# sx1509-breakout_mount_remap5.net
KiCad netlist of a schematic drawn in EAGLE
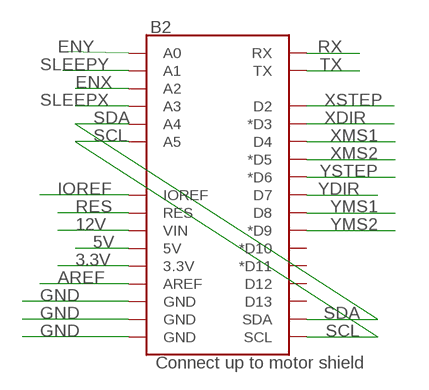
[diagram p0: schematic, sheet 1, part 1 of 2]
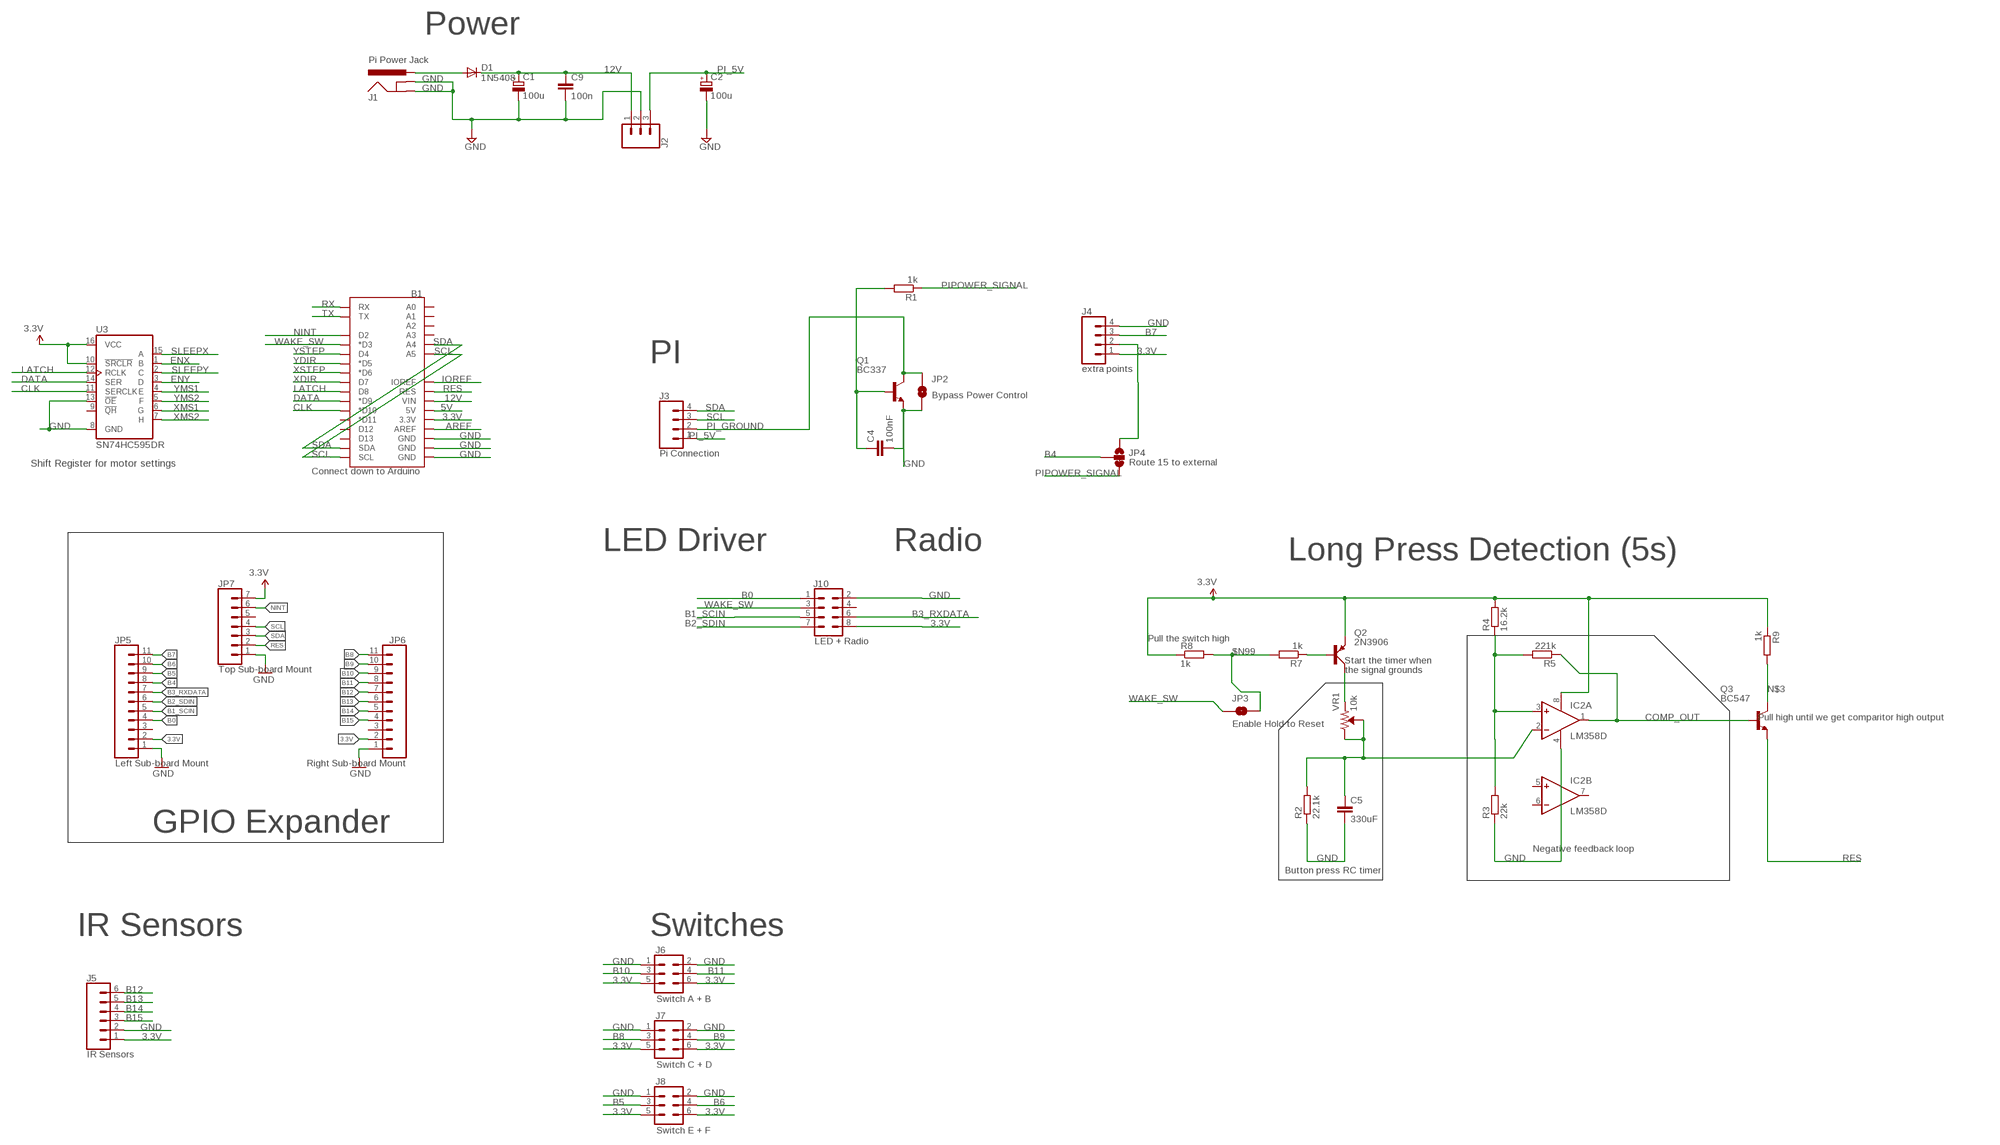
[diagram p1: schematic, sheet 1, part 2 of 2]

(export (version "E")
  (design (tool "Eeschema 10.0.6"))
  (components
    (comp (ref "B1")
      (value "Connect down to Arduino")
      (footprint "eagle-import:UNO_R3_SHIELD_NOLABELS")
      (libsource (lib "eagle-import") (part "ARDUINO_UNO_R3_SHIELDNOLABELS"))
    )
    (comp (ref "B2")
      (value "Connect up to motor shield")
      (footprint "eagle-import:UNO_R3_SHIELD_NOLABELS")
      (libsource (lib "eagle-import") (part "ARDUINO_UNO_R3_SHIELDNOLABELS"))
    )
    (comp (ref "C1")
      (value "100u")
      (footprint "eagle-import:E2-5")
      (libsource (lib "eagle-import") (part "CPOL-EUE2-5"))
    )
    (comp (ref "C2")
      (value "100u")
      (footprint "eagle-import:E2-5")
      (libsource (lib "eagle-import") (part "CPOL-EUE2-5"))
    )
    (comp (ref "C4")
      (value "100nF")
      (footprint "eagle-import:C0805")
      (libsource (lib "eagle-import") (part "resistor_348_C-EUC0805"))
    )
    (comp (ref "C5")
      (value "330uF")
      (footprint "eagle-import:C0805")
      (libsource (lib "eagle-import") (part "resistor_348_C-EUC0805"))
    )
    (comp (ref "C9")
      (value "100n")
      (footprint "eagle-import:C0805")
      (libsource (lib "eagle-import") (part "C-EUC0805"))
    )
    (comp (ref "D1")
      (value "1N5408")
      (footprint "eagle-import:DO15-12")
      (libsource (lib "eagle-import") (part "1N5408"))
    )
    (comp (ref "IC2")
      (value "LM358D")
      (footprint "eagle-import:SO08")
      (libsource (lib "eagle-import") (part "LM358D"))
    )
    (comp (ref "J1")
      (value "Pi Power Jack")
      (footprint "eagle-import:POWER_JACK_PTH_BREAD")
      (libsource (lib "eagle-import") (part "POWER_JACKPTH_BREAD"))
    )
    (comp (ref "J2")
      (value "Header - Right angled, female")
      (footprint "eagle-import:1X03")
      (libsource (lib "eagle-import") (part "CONN_031X03_2.54MM_RA_FEMALE"))
    )
    (comp (ref "J3")
      (value "Pi Connection")
      (footprint "eagle-import:1X04_1.24MM_RA_MALE")
      (libsource (lib "eagle-import") (part "CONN_041X04_1.24MM_RA_MALE"))
    )
    (comp (ref "J4")
      (value "extra points")
      (footprint "eagle-import:1X04_1.24MM_RA_MALE")
      (libsource (lib "eagle-import") (part "CONN_041X04_1.24MM_RA_MALE"))
    )
    (comp (ref "J5")
      (value "IR Sensors")
      (footprint "eagle-import:1X06")
      (libsource (lib "eagle-import") (part "CONN_06SILK_FEMALE_PTH"))
    )
    (comp (ref "J6")
      (value "Switch A + B")
      (footprint "eagle-import:2X3")
      (libsource (lib "eagle-import") (part "CONN_03X22X03_2.54MM_RA_MALE"))
    )
    (comp (ref "J7")
      (value "Switch C + D")
      (footprint "eagle-import:2X3")
      (libsource (lib "eagle-import") (part "CONN_03X22X03_2.54MM_RA_MALE"))
    )
    (comp (ref "J8")
      (value "Switch E + F")
      (footprint "eagle-import:2X3")
      (libsource (lib "eagle-import") (part "CONN_03X22X03_2.54MM_RA_MALE"))
    )
    (comp (ref "J10")
      (value "LED + Radio")
      (footprint "eagle-import:2X4")
      (libsource (lib "eagle-import") (part "CONN_04X22X4_1.24MM_RA_MALE"))
    )
    (comp (ref "JP2")
      (value "Bypass Power Control")
      (footprint "eagle-import:SMT-JUMPER_2_NO_SILK_ROUND")
      (libsource (lib "eagle-import") (part "JUMPER-SMT_2_NO_SILK_ROUND"))
    )
    (comp (ref "JP3")
      (value "Enable Hold to Reset")
      (footprint "eagle-import:SMT-JUMPER_2_NC_TRACE_SILK")
      (libsource (lib "eagle-import") (part "JUMPER-SMT_2_NC_TRACE_SILK"))
    )
    (comp (ref "JP4")
      (value "Route 15 to external")
      (footprint "eagle-import:SMT-JUMPER_3_1-NC_TRACE_SILK")
      (libsource (lib "eagle-import") (part "JUMPER-SMT_3_1-NC_TRACE_SILK"))
    )
    (comp (ref "JP5")
      (value "Left Sub-board Mount")
      (footprint "eagle-import:1X11")
      (libsource (lib "eagle-import") (part "CONN_111X11_2.54MM_FEMALE"))
    )
    (comp (ref "JP6")
      (value "Right Sub-board Mount")
      (footprint "eagle-import:1X11")
      (libsource (lib "eagle-import") (part "CONN_111X11_2.54MM_FEMALE"))
    )
    (comp (ref "JP7")
      (value "Top Sub-board Mount")
      (footprint "eagle-import:1X07")
      (libsource (lib "eagle-import") (part "CONN_071X07_2.54MM_FEMALE"))
    )
    (comp (ref "Q1")
      (value "BC337")
      (footprint "eagle-import:TO92")
      (libsource (lib "eagle-import") (part "BC337"))
    )
    (comp (ref "Q2")
      (value "2N3906")
      (footprint "eagle-import:TO92D")
      (libsource (lib "eagle-import") (part "2N3906"))
    )
    (comp (ref "Q3")
      (value "BC547")
      (footprint "eagle-import:TO92")
      (fields (field (name "NOTE") "Pull high until we get comparitor high output"))
      (libsource (lib "eagle-import") (part "BC547"))
    )
    (comp (ref "R1")
      (value "1k")
      (footprint "eagle-import:M0805")
      (libsource (lib "eagle-import") (part "R-EU_M0805"))
    )
    (comp (ref "R2")
      (value "22.1k")
      (footprint "eagle-import:M0805")
      (libsource (lib "eagle-import") (part "R-EU_M0805"))
    )
    (comp (ref "R3")
      (value "22k")
      (footprint "eagle-import:M0805")
      (libsource (lib "eagle-import") (part "R-EU_M0805"))
    )
    (comp (ref "R4")
      (value "16.2k")
      (footprint "eagle-import:M0805")
      (libsource (lib "eagle-import") (part "R-EU_M0805"))
    )
    (comp (ref "R5")
      (value "221k")
      (footprint "eagle-import:M0805")
      (libsource (lib "eagle-import") (part "R-EU_M0805"))
    )
    (comp (ref "R7")
      (value "1k")
      (footprint "eagle-import:M0805")
      (libsource (lib "eagle-import") (part "R-EU_M0805"))
    )
    (comp (ref "R8")
      (value "1k")
      (footprint "eagle-import:M0805")
      (fields (field (name "NOTE") "Pull the switch high"))
      (libsource (lib "eagle-import") (part "R-EU_M0805"))
    )
    (comp (ref "R9")
      (value "1k")
      (footprint "eagle-import:M0805")
      (libsource (lib "eagle-import") (part "R-EU_M0805"))
    )
    (comp (ref "U3")
      (value "SN74HC595DR")
      (footprint "eagle-import:SO16")
      (libsource (lib "eagle-import") (part "SN74HC595DHC"))
    )
    (comp (ref "VR1")
      (value "10k")
      (footprint "eagle-import:TRIMPOT-PTH-3386U")
      (libsource (lib "eagle-import") (part "TRIMPOT-PTH-10MM-KNOB-1/2W-10%"))
    )
  )
  (nets
    (net (code "1") (name "/$N99") (class "Default")
      (node (ref "JP3") (pin "2") (pinfunction "2_2") (pintype "passive"))
      (node (ref "R7") (pin "2") (pinfunction "2_2") (pintype "passive"))
      (node (ref "R8") (pin "2") (pinfunction "2_2") (pintype "passive"))
    )
    (net (code "2") (name "/5V") (class "Default")
      (node (ref "B1") (pin "5V") (pinfunction "5V_5V") (pintype "bidirectional"))
      (node (ref "B2") (pin "5V") (pinfunction "5V_5V") (pintype "bidirectional"))
    )
    (net (code "3") (name "/12V") (class "Default")
      (node (ref "B1") (pin "VIN") (pinfunction "VIN_VIN") (pintype "bidirectional"))
      (node (ref "B2") (pin "VIN") (pinfunction "VIN_VIN") (pintype "bidirectional"))
      (node (ref "C1") (pin "+") (pinfunction "+_+") (pintype "passive"))
      (node (ref "C9") (pin "1") (pinfunction "1_1") (pintype "passive"))
      (node (ref "D1") (pin "C") (pinfunction "C_C") (pintype "passive"))
      (node (ref "J2") (pin "1") (pinfunction "1_1") (pintype "passive"))
    )
    (net (code "4") (name "/AREF") (class "Default")
      (node (ref "B1") (pin "AREF") (pinfunction "AREF_AREF") (pintype "bidirectional"))
      (node (ref "B2") (pin "AREF") (pinfunction "AREF_AREF") (pintype "bidirectional"))
    )
    (net (code "5") (name "/CLK") (class "Default")
      (node (ref "B1") (pin "D10") (pinfunction "*D10_D10") (pintype "bidirectional"))
      (node (ref "U3") (pin "11") (pinfunction "SERCLK_11") (pintype "input"))
    )
    (net (code "6") (name "/COMP_OUT") (class "Default")
      (node (ref "IC2") (pin "1") (pinfunction "OUT_1") (pintype "output"))
      (node (ref "Q3") (pin "2") (pinfunction "B_2") (pintype "passive"))
      (node (ref "R5") (pin "1") (pinfunction "1_1") (pintype "passive"))
    )
    (net (code "7") (name "/DATA") (class "Default")
      (node (ref "B1") (pin "D9") (pinfunction "*D9_D9") (pintype "bidirectional"))
      (node (ref "U3") (pin "14") (pinfunction "SER_14") (pintype "input"))
    )
    (net (code "8") (name "/ENX") (class "Default")
      (node (ref "B2") (pin "A2") (pinfunction "A2_A2") (pintype "bidirectional"))
      (node (ref "U3") (pin "1") (pinfunction "B_1") (pintype "tri_state"))
    )
    (net (code "9") (name "/ENY") (class "Default")
      (node (ref "B2") (pin "A0") (pinfunction "A0_A0") (pintype "bidirectional"))
      (node (ref "U3") (pin "3") (pinfunction "D_3") (pintype "tri_state"))
    )
    (net (code "10") (name "/IOREF") (class "Default")
      (node (ref "B1") (pin "IOREF") (pinfunction "IOREF_IOREF") (pintype "bidirectional"))
      (node (ref "B2") (pin "IOREF") (pinfunction "IOREF_IOREF") (pintype "bidirectional"))
    )
    (net (code "11") (name "/LATCH") (class "Default")
      (node (ref "B1") (pin "D8") (pinfunction "D8_D8") (pintype "bidirectional"))
      (node (ref "U3") (pin "12") (pinfunction "RCLK_12") (pintype "input"))
    )
    (net (code "12") (name "/N$3") (class "Default")
      (node (ref "Q3") (pin "3") (pinfunction "C_3") (pintype "passive"))
      (node (ref "R9") (pin "2") (pinfunction "2_2") (pintype "passive"))
    )
    (net (code "13") (name "/PIPOWER_SIGNAL") (class "Default")
      (node (ref "JP4") (pin "3") (pinfunction "3_3") (pintype "passive"))
      (node (ref "R1") (pin "1") (pinfunction "1_1") (pintype "passive"))
    )
    (net (code "14") (name "/PI_5V") (class "Default")
      (node (ref "C2") (pin "+") (pinfunction "+_+") (pintype "passive"))
      (node (ref "J2") (pin "3") (pinfunction "3_3") (pintype "passive"))
      (node (ref "J3") (pin "1") (pinfunction "1_1") (pintype "passive"))
    )
    (net (code "15") (name "/PI_GROUND") (class "Default")
      (node (ref "J3") (pin "2") (pinfunction "2_2") (pintype "passive"))
      (node (ref "JP2") (pin "1") (pinfunction "1_1") (pintype "passive"))
      (node (ref "Q1") (pin "3") (pinfunction "C_3") (pintype "passive"))
    )
    (net (code "16") (name "/RX") (class "Default")
      (node (ref "B1") (pin "RX") (pinfunction "RX_RX") (pintype "bidirectional"))
      (node (ref "B2") (pin "RX") (pinfunction "RX_RX") (pintype "bidirectional"))
    )
    (net (code "17") (name "/SLEEPX") (class "Default")
      (node (ref "B2") (pin "A3") (pinfunction "A3_A3") (pintype "bidirectional"))
      (node (ref "U3") (pin "15") (pinfunction "A_15") (pintype "tri_state"))
    )
    (net (code "18") (name "/SLEEPY") (class "Default")
      (node (ref "B2") (pin "A1") (pinfunction "A1_A1") (pintype "bidirectional"))
      (node (ref "U3") (pin "2") (pinfunction "C_2") (pintype "tri_state"))
    )
    (net (code "19") (name "/TX") (class "Default")
      (node (ref "B1") (pin "TX") (pinfunction "TX_TX") (pintype "bidirectional"))
      (node (ref "B2") (pin "TX") (pinfunction "TX_TX") (pintype "bidirectional"))
    )
    (net (code "20") (name "/WAKE_SW") (class "Default")
      (node (ref "B1") (pin "D3") (pinfunction "*D3_D3") (pintype "bidirectional"))
      (node (ref "J10") (pin "3") (pinfunction "3_3") (pintype "passive"))
      (node (ref "JP3") (pin "1") (pinfunction "1_1") (pintype "passive"))
    )
    (net (code "21") (name "/XDIR") (class "Default")
      (node (ref "B1") (pin "D7") (pinfunction "D7_D7") (pintype "bidirectional"))
      (node (ref "B2") (pin "D3") (pinfunction "*D3_D3") (pintype "bidirectional"))
    )
    (net (code "22") (name "/XMS1") (class "Default")
      (node (ref "B2") (pin "D4") (pinfunction "D4_D4") (pintype "bidirectional"))
      (node (ref "U3") (pin "6") (pinfunction "G_6") (pintype "tri_state"))
    )
    (net (code "23") (name "/XMS2") (class "Default")
      (node (ref "B2") (pin "D5") (pinfunction "*D5_D5") (pintype "bidirectional"))
      (node (ref "U3") (pin "7") (pinfunction "H_7") (pintype "tri_state"))
    )
    (net (code "24") (name "/XSTEP") (class "Default")
      (node (ref "B1") (pin "D6") (pinfunction "*D6_D6") (pintype "bidirectional"))
      (node (ref "B2") (pin "D2") (pinfunction "D2_D2") (pintype "bidirectional"))
    )
    (net (code "25") (name "/YDIR") (class "Default")
      (node (ref "B1") (pin "D5") (pinfunction "*D5_D5") (pintype "bidirectional"))
      (node (ref "B2") (pin "D7") (pinfunction "D7_D7") (pintype "bidirectional"))
    )
    (net (code "26") (name "/YMS1") (class "Default")
      (node (ref "B2") (pin "D8") (pinfunction "D8_D8") (pintype "bidirectional"))
      (node (ref "U3") (pin "4") (pinfunction "E_4") (pintype "tri_state"))
    )
    (net (code "27") (name "/YMS2") (class "Default")
      (node (ref "B2") (pin "D9") (pinfunction "*D9_D9") (pintype "bidirectional"))
      (node (ref "U3") (pin "5") (pinfunction "F_5") (pintype "tri_state"))
    )
    (net (code "28") (name "/YSTEP") (class "Default")
      (node (ref "B1") (pin "D4") (pinfunction "D4_D4") (pintype "bidirectional"))
      (node (ref "B2") (pin "D6") (pinfunction "*D6_D6") (pintype "bidirectional"))
    )
    (net (code "29") (name "3.3V") (class "Default")
      (node (ref "B1") (pin "3.3V") (pinfunction "3.3V_3.3V") (pintype "bidirectional"))
      (node (ref "B2") (pin "3.3V") (pinfunction "3.3V_3.3V") (pintype "bidirectional"))
      (node (ref "IC2") (pin "8") (pinfunction "V+_8") (pintype "power_in"))
      (node (ref "J10") (pin "8") (pinfunction "8_8") (pintype "passive"))
      (node (ref "J4") (pin "1") (pinfunction "1_1") (pintype "passive"))
      (node (ref "J5") (pin "1") (pinfunction "1_1") (pintype "passive"))
      (node (ref "J6") (pin "5") (pinfunction "5_5") (pintype "bidirectional"))
      (node (ref "J6") (pin "6") (pinfunction "6_6") (pintype "bidirectional"))
      (node (ref "J7") (pin "5") (pinfunction "5_5") (pintype "bidirectional"))
      (node (ref "J7") (pin "6") (pinfunction "6_6") (pintype "bidirectional"))
      (node (ref "J8") (pin "5") (pinfunction "5_5") (pintype "bidirectional"))
      (node (ref "J8") (pin "6") (pinfunction "6_6") (pintype "bidirectional"))
      (node (ref "JP5") (pin "2") (pinfunction "2_2") (pintype "passive"))
      (node (ref "JP6") (pin "2") (pinfunction "2_2") (pintype "passive"))
      (node (ref "JP7") (pin "7") (pinfunction "7_7") (pintype "passive"))
      (node (ref "Q2") (pin "E") (pinfunction "E_E") (pintype "passive"))
      (node (ref "R4") (pin "2") (pinfunction "2_2") (pintype "passive"))
      (node (ref "R8") (pin "1") (pinfunction "1_1") (pintype "passive"))
      (node (ref "R9") (pin "1") (pinfunction "1_1") (pintype "passive"))
      (node (ref "U3") (pin "10") (pinfunction "~{SRCLR}_10") (pintype "input"))
      (node (ref "U3") (pin "16") (pinfunction "VCC_16") (pintype "power_in"))
    )
    (net (code "30") (name "B0") (class "Default")
      (node (ref "J10") (pin "1") (pinfunction "1_1") (pintype "passive"))
      (node (ref "JP5") (pin "4") (pinfunction "4_4") (pintype "passive"))
    )
    (net (code "31") (name "B1_SCIN") (class "Default")
      (node (ref "J10") (pin "5") (pinfunction "5_5") (pintype "passive"))
      (node (ref "JP5") (pin "5") (pinfunction "5_5") (pintype "passive"))
    )
    (net (code "32") (name "B2_SDIN") (class "Default")
      (node (ref "J10") (pin "7") (pinfunction "7_7") (pintype "passive"))
      (node (ref "JP5") (pin "6") (pinfunction "6_6") (pintype "passive"))
    )
    (net (code "33") (name "B3_RXDATA") (class "Default")
      (node (ref "J10") (pin "6") (pinfunction "6_6") (pintype "passive"))
      (node (ref "JP5") (pin "7") (pinfunction "7_7") (pintype "passive"))
    )
    (net (code "34") (name "B4") (class "Default")
      (node (ref "JP4") (pin "2") (pinfunction "2_2") (pintype "passive"))
      (node (ref "JP5") (pin "8") (pinfunction "8_8") (pintype "passive"))
    )
    (net (code "35") (name "B5") (class "Default")
      (node (ref "J8") (pin "3") (pinfunction "3_3") (pintype "bidirectional"))
      (node (ref "JP5") (pin "9") (pinfunction "9_9") (pintype "passive"))
    )
    (net (code "36") (name "B6") (class "Default")
      (node (ref "J8") (pin "4") (pinfunction "4_4") (pintype "bidirectional"))
      (node (ref "JP5") (pin "10") (pinfunction "10_10") (pintype "passive"))
    )
    (net (code "37") (name "B7") (class "Default")
      (node (ref "J4") (pin "3") (pinfunction "3_3") (pintype "passive"))
      (node (ref "JP5") (pin "11") (pinfunction "11_11") (pintype "passive"))
    )
    (net (code "38") (name "B8") (class "Default")
      (node (ref "J7") (pin "3") (pinfunction "3_3") (pintype "bidirectional"))
      (node (ref "JP6") (pin "11") (pinfunction "11_11") (pintype "passive"))
    )
    (net (code "39") (name "B9") (class "Default")
      (node (ref "J7") (pin "4") (pinfunction "4_4") (pintype "bidirectional"))
      (node (ref "JP6") (pin "10") (pinfunction "10_10") (pintype "passive"))
    )
    (net (code "40") (name "B10") (class "Default")
      (node (ref "J6") (pin "3") (pinfunction "3_3") (pintype "bidirectional"))
      (node (ref "JP6") (pin "9") (pinfunction "9_9") (pintype "passive"))
    )
    (net (code "41") (name "B11") (class "Default")
      (node (ref "J6") (pin "4") (pinfunction "4_4") (pintype "bidirectional"))
      (node (ref "JP6") (pin "8") (pinfunction "8_8") (pintype "passive"))
    )
    (net (code "42") (name "B12") (class "Default")
      (node (ref "J5") (pin "6") (pinfunction "6_6") (pintype "passive"))
      (node (ref "JP6") (pin "7") (pinfunction "7_7") (pintype "passive"))
    )
    (net (code "43") (name "B13") (class "Default")
      (node (ref "J5") (pin "5") (pinfunction "5_5") (pintype "passive"))
      (node (ref "JP6") (pin "6") (pinfunction "6_6") (pintype "passive"))
    )
    (net (code "44") (name "B14") (class "Default")
      (node (ref "J5") (pin "4") (pinfunction "4_4") (pintype "passive"))
      (node (ref "JP6") (pin "5") (pinfunction "5_5") (pintype "passive"))
    )
    (net (code "45") (name "B15") (class "Default")
      (node (ref "J5") (pin "3") (pinfunction "3_3") (pintype "passive"))
      (node (ref "JP6") (pin "4") (pinfunction "4_4") (pintype "passive"))
    )
    (net (code "46") (name "GND") (class "Default")
      (node (ref "B1") (pin "GND@0") (pinfunction "GND_GND@0") (pintype "bidirectional"))
      (node (ref "B1") (pin "GND@1") (pinfunction "GND_GND@1") (pintype "bidirectional"))
      (node (ref "B1") (pin "GND@2") (pinfunction "GND_GND@2") (pintype "bidirectional"))
      (node (ref "B2") (pin "GND@0") (pinfunction "GND_GND@0") (pintype "bidirectional"))
      (node (ref "B2") (pin "GND@1") (pinfunction "GND_GND@1") (pintype "bidirectional"))
      (node (ref "B2") (pin "GND@2") (pinfunction "GND_GND@2") (pintype "bidirectional"))
      (node (ref "C1") (pin "-") (pinfunction "-_-") (pintype "passive"))
      (node (ref "C2") (pin "-") (pinfunction "-_-") (pintype "passive"))
      (node (ref "C4") (pin "2") (pinfunction "2_2") (pintype "passive"))
      (node (ref "C5") (pin "2") (pinfunction "2_2") (pintype "passive"))
      (node (ref "C9") (pin "2") (pinfunction "2_2") (pintype "passive"))
      (node (ref "IC2") (pin "4") (pinfunction "V-_4") (pintype "power_in"))
      (node (ref "J1") (pin "GND") (pinfunction "GND_GND") (pintype "bidirectional"))
      (node (ref "J1") (pin "GNDBREAK") (pinfunction "GNDBREAK_GNDBREAK") (pintype "bidirectional"))
      (node (ref "J10") (pin "2") (pinfunction "2_2") (pintype "passive"))
      (node (ref "J2") (pin "2") (pinfunction "2_2") (pintype "passive"))
      (node (ref "J4") (pin "4") (pinfunction "4_4") (pintype "passive"))
      (node (ref "J5") (pin "2") (pinfunction "2_2") (pintype "passive"))
      (node (ref "J6") (pin "1") (pinfunction "1_1") (pintype "bidirectional"))
      (node (ref "J6") (pin "2") (pinfunction "2_2") (pintype "bidirectional"))
      (node (ref "J7") (pin "1") (pinfunction "1_1") (pintype "bidirectional"))
      (node (ref "J7") (pin "2") (pinfunction "2_2") (pintype "bidirectional"))
      (node (ref "J8") (pin "1") (pinfunction "1_1") (pintype "bidirectional"))
      (node (ref "J8") (pin "2") (pinfunction "2_2") (pintype "bidirectional"))
      (node (ref "JP2") (pin "2") (pinfunction "2_2") (pintype "passive"))
      (node (ref "JP5") (pin "1") (pinfunction "1_1") (pintype "passive"))
      (node (ref "JP6") (pin "1") (pinfunction "1_1") (pintype "passive"))
      (node (ref "JP7") (pin "1") (pinfunction "1_1") (pintype "passive"))
      (node (ref "Q1") (pin "1") (pinfunction "E_1") (pintype "passive"))
      (node (ref "R2") (pin "1") (pinfunction "1_1") (pintype "passive"))
      (node (ref "R3") (pin "1") (pinfunction "1_1") (pintype "passive"))
      (node (ref "U3") (pin "13") (pinfunction "~{OE}_13") (pintype "input"))
      (node (ref "U3") (pin "8") (pinfunction "GND_8") (pintype "power_in"))
    )
    (net (code "47") (name "NINT") (class "Default")
      (node (ref "B1") (pin "D2") (pinfunction "D2_D2") (pintype "bidirectional"))
      (node (ref "JP7") (pin "6") (pinfunction "6_6") (pintype "passive"))
    )
    (net (code "48") (name "Net-(D1-PadA)") (class "Default")
      (node (ref "D1") (pin "A") (pinfunction "A_A") (pintype "passive"))
      (node (ref "J1") (pin "PWR") (pinfunction "PWR_PWR") (pintype "bidirectional"))
    )
    (net (code "49") (name "Net-(IC2A-+IN)") (class "Default")
      (node (ref "IC2") (pin "3") (pinfunction "+IN_3") (pintype "input"))
      (node (ref "R3") (pin "2") (pinfunction "2_2") (pintype "passive"))
      (node (ref "R4") (pin "1") (pinfunction "1_1") (pintype "passive"))
      (node (ref "R5") (pin "2") (pinfunction "2_2") (pintype "passive"))
    )
    (net (code "50") (name "Net-(IC2A--IN)") (class "Default")
      (node (ref "C5") (pin "1") (pinfunction "1_1") (pintype "passive"))
      (node (ref "IC2") (pin "2") (pinfunction "-IN_2") (pintype "input"))
      (node (ref "R2") (pin "2") (pinfunction "2_2") (pintype "passive"))
      (node (ref "VR1") (pin "2") (pinfunction "WIPER_2") (pintype "passive"))
      (node (ref "VR1") (pin "3") (pinfunction "CW_3") (pintype "passive"))
    )
    (net (code "51") (name "Net-(J4-Pad2)") (class "Default")
      (node (ref "J4") (pin "2") (pinfunction "2_2") (pintype "passive"))
      (node (ref "JP4") (pin "1") (pinfunction "1_1") (pintype "passive"))
    )
    (net (code "52") (name "Net-(Q1-B)") (class "Default")
      (node (ref "C4") (pin "1") (pinfunction "1_1") (pintype "passive"))
      (node (ref "Q1") (pin "2") (pinfunction "B_2") (pintype "passive"))
      (node (ref "R1") (pin "2") (pinfunction "2_2") (pintype "passive"))
    )
    (net (code "53") (name "Net-(Q2-PadB)") (class "Default")
      (node (ref "Q2") (pin "B") (pinfunction "B_B") (pintype "passive"))
      (node (ref "R7") (pin "1") (pinfunction "1_1") (pintype "passive"))
    )
    (net (code "54") (name "Net-(VR1-CCW)") (class "Default")
      (node (ref "Q2") (pin "C") (pinfunction "C_C") (pintype "passive"))
      (node (ref "VR1") (pin "1") (pinfunction "CCW_1") (pintype "passive"))
    )
    (net (code "55") (name "RES") (class "Default")
      (node (ref "B1") (pin "RES") (pinfunction "RES_RES") (pintype "bidirectional"))
      (node (ref "B2") (pin "RES") (pinfunction "RES_RES") (pintype "bidirectional"))
      (node (ref "JP7") (pin "2") (pinfunction "2_2") (pintype "passive"))
      (node (ref "Q3") (pin "1") (pinfunction "E_1") (pintype "passive"))
    )
    (net (code "56") (name "SCL") (class "Default")
      (node (ref "B1") (pin "A5") (pinfunction "A5_A5") (pintype "bidirectional"))
      (node (ref "B1") (pin "SCL") (pinfunction "SCL_SCL") (pintype "bidirectional"))
      (node (ref "B2") (pin "A5") (pinfunction "A5_A5") (pintype "bidirectional"))
      (node (ref "B2") (pin "SCL") (pinfunction "SCL_SCL") (pintype "bidirectional"))
      (node (ref "J3") (pin "3") (pinfunction "3_3") (pintype "passive"))
      (node (ref "JP7") (pin "4") (pinfunction "4_4") (pintype "passive"))
    )
    (net (code "57") (name "SDA") (class "Default")
      (node (ref "B1") (pin "A4") (pinfunction "A4_A4") (pintype "bidirectional"))
      (node (ref "B1") (pin "SDA") (pinfunction "SDA_SDA") (pintype "bidirectional"))
      (node (ref "B2") (pin "A4") (pinfunction "A4_A4") (pintype "bidirectional"))
      (node (ref "B2") (pin "SDA") (pinfunction "SDA_SDA") (pintype "bidirectional"))
      (node (ref "J3") (pin "4") (pinfunction "4_4") (pintype "passive"))
      (node (ref "JP7") (pin "3") (pinfunction "3_3") (pintype "passive"))
    )
    (net (code "58") (name "unconnected-(B1-*D11-PadD11)") (class "Default")
      (node (ref "B1") (pin "D11") (pinfunction "*D11_D11") (pintype "bidirectional"))
    )
    (net (code "59") (name "unconnected-(B1-PadA0)") (class "Default")
      (node (ref "B1") (pin "A0") (pinfunction "A0_A0") (pintype "bidirectional"))
    )
    (net (code "60") (name "unconnected-(B1-PadA1)") (class "Default")
      (node (ref "B1") (pin "A1") (pinfunction "A1_A1") (pintype "bidirectional"))
    )
    (net (code "61") (name "unconnected-(B1-PadA2)") (class "Default")
      (node (ref "B1") (pin "A2") (pinfunction "A2_A2") (pintype "bidirectional"))
    )
    (net (code "62") (name "unconnected-(B1-PadA3)") (class "Default")
      (node (ref "B1") (pin "A3") (pinfunction "A3_A3") (pintype "bidirectional"))
    )
    (net (code "63") (name "unconnected-(B1-PadD12)") (class "Default")
      (node (ref "B1") (pin "D12") (pinfunction "D12_D12") (pintype "bidirectional"))
    )
    (net (code "64") (name "unconnected-(B1-PadD13)") (class "Default")
      (node (ref "B1") (pin "D13") (pinfunction "D13_D13") (pintype "bidirectional"))
    )
    (net (code "65") (name "unconnected-(B2-*D10-PadD10)") (class "Default")
      (node (ref "B2") (pin "D10") (pinfunction "*D10_D10") (pintype "bidirectional"))
    )
    (net (code "66") (name "unconnected-(B2-*D11-PadD11)") (class "Default")
      (node (ref "B2") (pin "D11") (pinfunction "*D11_D11") (pintype "bidirectional"))
    )
    (net (code "67") (name "unconnected-(B2-PadD12)") (class "Default")
      (node (ref "B2") (pin "D12") (pinfunction "D12_D12") (pintype "bidirectional"))
    )
    (net (code "68") (name "unconnected-(B2-PadD13)") (class "Default")
      (node (ref "B2") (pin "D13") (pinfunction "D13_D13") (pintype "bidirectional"))
    )
    (net (code "69") (name "unconnected-(IC2B-+IN-Pad5)") (class "Default")
      (node (ref "IC2") (pin "5") (pinfunction "+IN_5") (pintype "input"))
    )
    (net (code "70") (name "unconnected-(IC2B--IN-Pad6)") (class "Default")
      (node (ref "IC2") (pin "6") (pinfunction "-IN_6") (pintype "input"))
    )
    (net (code "71") (name "unconnected-(IC2B-OUT-Pad7)") (class "Default")
      (node (ref "IC2") (pin "7") (pinfunction "OUT_7") (pintype "output"))
    )
    (net (code "72") (name "unconnected-(J10-Pad4)") (class "Default")
      (node (ref "J10") (pin "4") (pinfunction "4_4") (pintype "passive"))
    )
    (net (code "73") (name "unconnected-(JP5-Pad3)") (class "Default")
      (node (ref "JP5") (pin "3") (pinfunction "3_3") (pintype "passive"))
    )
    (net (code "74") (name "unconnected-(JP6-Pad3)") (class "Default")
      (node (ref "JP6") (pin "3") (pinfunction "3_3") (pintype "passive"))
    )
    (net (code "75") (name "unconnected-(JP7-Pad5)") (class "Default")
      (node (ref "JP7") (pin "5") (pinfunction "5_5") (pintype "passive"))
    )
    (net (code "76") (name "unconnected-(U3-~{QH}-Pad9)") (class "Default")
      (node (ref "U3") (pin "9") (pinfunction "~{QH}_9") (pintype "output"))
    )
  )
)
